# 3V8_Power_Regulator.net
KiCad netlist of a schematic drawn in Altium Designer
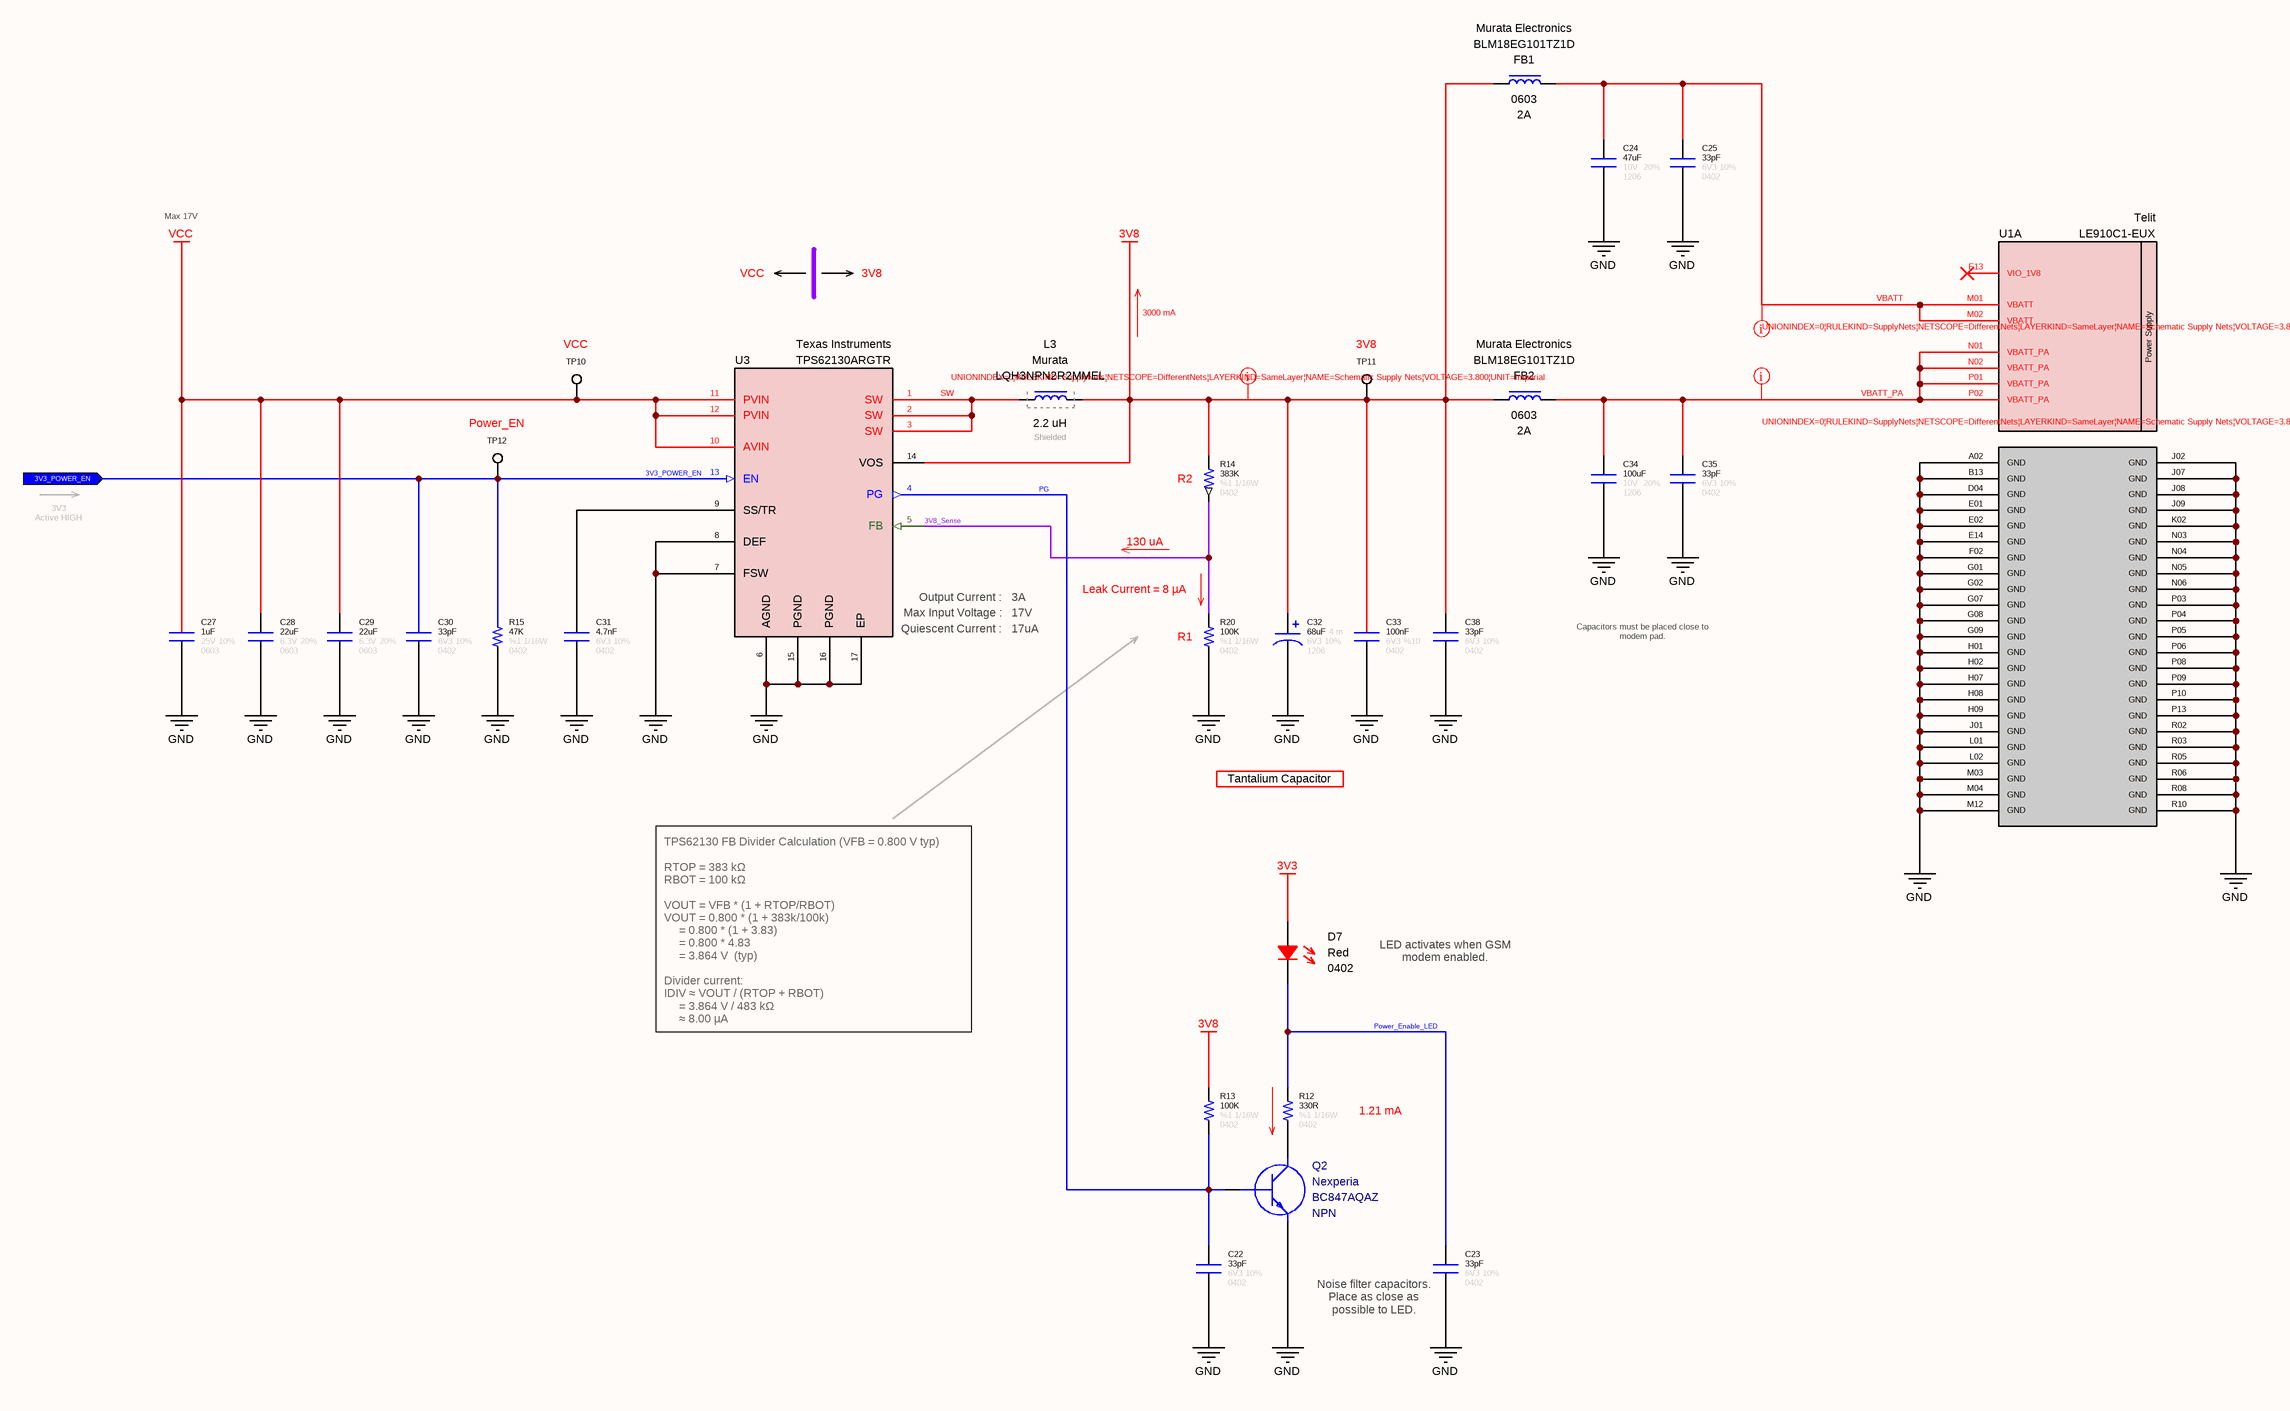
[diagram p0: 3V8_Power_Regulator.SchDoc]

(export (version "E")
  (design (tool "Eeschema 10.0.6"))
  (components
    (comp (ref "C22")
      (value "33pF")
      (footprint "CAPACITOR_0402")
      (description "Capacitor - 33pF [0402] (Ceramic)")
      (fields
        (field (name "MANUFACTURER PART NUMBER") "C0402C330J9RACAUTO")
        (field (name "TOLERANCE") "10%")
        (field (name "CASE") "0402")
        (field (name "VOLTAGE") "6V3")
      )
      (libsource (lib "P101DA_Library") (part "Capacitor - 33pF [0402-6V3]"))
    )
    (comp (ref "C23")
      (value "33pF")
      (footprint "CAPACITOR_0402")
      (description "Capacitor - 33pF [0402] (Ceramic)")
      (fields
        (field (name "MANUFACTURER PART NUMBER") "C0402C330J9RACAUTO")
        (field (name "TOLERANCE") "10%")
        (field (name "CASE") "0402")
        (field (name "VOLTAGE") "6V3")
      )
      (libsource (lib "P101DA_Library") (part "Capacitor - 33pF [0402-6V3]"))
    )
    (comp (ref "C24")
      (value "47uF")
      (footprint "CAPACITOR_1206")
      (description "Multilayer Ceramic Capacitors MLCC - SMD/SMT 47UF 10V 20% 1206")
      (fields
        (field (name "MANUFACTURER PART NUMBER") "C1206C476M8PAC")
        (field (name "TOLERANCE") "20%")
        (field (name "CASE") "1206")
        (field (name "VOLTAGE") "10V")
        (field (name "Comment") "Capacitor - 47uF [1206] (Ceramic)")
      )
      (libsource (lib "Akkoyun") (part "Capacitor - 47uF [1206-10V]"))
    )
    (comp (ref "C25")
      (value "33pF")
      (footprint "CAPACITOR_0402")
      (description "Capacitor - 33pF [0402] (Ceramic)")
      (fields
        (field (name "MANUFACTURER PART NUMBER") "C0402C330J9RACAUTO")
        (field (name "TOLERANCE") "10%")
        (field (name "CASE") "0402")
        (field (name "VOLTAGE") "6V3")
      )
      (libsource (lib "Akkoyun") (part "Capacitor - 33pF [0402-6V3]"))
    )
    (comp (ref "C27")
      (value "1uF")
      (footprint "CAPACITOR_0402")
      (description "Multilayer Ceramic Capacitors - SMD - 25V 1uF X7R 0603 10%")
      (fields
        (field (name "MANUFACTURER PART NUMBER") "GCJ188R71E105KA01D")
        (field (name "TOLERANCE") "10%")
        (field (name "CASE") "0603")
        (field (name "VOLTAGE") "25V")
        (field (name "Comment") "Capacitor - 1uF [0603] (Ceramic)")
      )
      (libsource (lib "Akkoyun") (part "Capacitor - 1uF [0603-25V]"))
    )
    (comp (ref "C28")
      (value "22uF")
      (footprint "CAPACITOR_0603")
      (description "Capacitor (MLCC) - 22uF / 6V3 / 0603")
      (fields
        (field (name "MANUFACTURER PART NUMBER") "GRM188R60J226MEA0D")
        (field (name "TOLERANCE") "20%")
        (field (name "CASE") "0603")
        (field (name "VOLTAGE") "6.3V")
        (field (name "Comment") "Capacitor - 22uF [0603] (MLCC)")
      )
      (libsource (lib "Akkoyun") (part "Capacitor - 22uF [0603-6V3]"))
    )
    (comp (ref "C29")
      (value "22uF")
      (footprint "CAPACITOR_0603")
      (description "Capacitor (MLCC) - 22uF / 6V3 / 0603")
      (fields
        (field (name "MANUFACTURER PART NUMBER") "GRM188R60J226MEA0D")
        (field (name "TOLERANCE") "20%")
        (field (name "CASE") "0603")
        (field (name "VOLTAGE") "6.3V")
        (field (name "Comment") "Capacitor - 22uF [0603] (MLCC)")
      )
      (libsource (lib "Akkoyun") (part "Capacitor - 22uF [0603-6V3]"))
    )
    (comp (ref "C30")
      (value "33pF")
      (footprint "CAPACITOR_0402")
      (description "Capacitor - 33pF [0402] (Ceramic)")
      (fields
        (field (name "MANUFACTURER PART NUMBER") "C0402C330J9RACAUTO")
        (field (name "TOLERANCE") "10%")
        (field (name "CASE") "0402")
        (field (name "VOLTAGE") "6V3")
      )
      (libsource (lib "Akkoyun") (part "Capacitor - 33pF [0402-6V3]"))
    )
    (comp (ref "C31")
      (value "4.7nF")
      (footprint "CAPACITOR_0402")
      (description "Capacitor (MLCC) - 4.7nF / 6V3 / 0402")
      (fields
        (field (name "MANUFACTURER PART NUMBER") "C0402C472K9RACTU")
        (field (name "TOLERANCE") "10%")
        (field (name "CASE") "0402")
        (field (name "VOLTAGE") "6V3")
        (field (name "Comment") "Capacitor - 4.7nF [0402] (MLCC)")
      )
      (libsource (lib "Akkoyun") (part "Capacitor - 4.7nF [0402-6V3]"))
    )
    (comp (ref "C32")
      (value "68uF")
      (footprint "CAPACITOR_1206 (Kemet)")
      (description "Capacitor (Tantalum) - 68uF / 6V3 / 1206")
      (fields
        (field (name "MANUFACTURER PART NUMBER") "T491A686K006AT")
        (field (name "ESR") "4 m")
        (field (name "TOLERANCE") "10%")
        (field (name "CASE") "1206")
        (field (name "VOLTAGE") "6V3")
        (field (name "Comment") "Capacitor - 68uF [1206] (Tantalum)")
      )
      (libsource (lib "Akkoyun") (part "Capacitor - 68uF [1206-6V3]"))
    )
    (comp (ref "C33")
      (value "100nF")
      (footprint "CAPACITOR_0402")
      (description "Capacitor - 100nF [0402-6V3] (Ceramic)")
      (fields
        (field (name "MANUFACTURER PART NUMBER") "04026D104KAT4A")
        (field (name "TOLERANCE") "%10")
        (field (name "VOLTAGE") "6V3")
        (field (name "CASE") "0402")
        (field (name "Comment") "Capacitor - 100nF [0402] (Ceramic)")
      )
      (libsource (lib "Akkoyun") (part "Capacitor - 100nF [0402-6V3]"))
    )
    (comp (ref "C34")
      (value "100uF")
      (footprint "CAPACITOR_1206")
      (description "Multilayer Ceramic Capacitors MLCC - SMD/SMT 100UF 10V 20% 1206")
      (fields
        (field (name "MANUFACTURER PART NUMBER") "GRM31CR61A107MEA8L")
        (field (name "TOLERANCE") "20%")
        (field (name "CASE") "1206")
        (field (name "VOLTAGE") "10V")
        (field (name "Comment") "Capacitor - 100uF [1206] (Ceramic)")
      )
      (libsource (lib "Akkoyun") (part "Capacitor - 100uF [1206-10V]"))
    )
    (comp (ref "C35")
      (value "33pF")
      (footprint "CAPACITOR_0402")
      (description "Capacitor - 33pF [0402] (Ceramic)")
      (fields
        (field (name "MANUFACTURER PART NUMBER") "C0402C330J9RACAUTO")
        (field (name "TOLERANCE") "10%")
        (field (name "CASE") "0402")
        (field (name "VOLTAGE") "6V3")
      )
      (libsource (lib "Akkoyun") (part "Capacitor - 33pF [0402-6V3]"))
    )
    (comp (ref "C38")
      (value "33pF")
      (footprint "CAPACITOR_0402")
      (description "Capacitor - 33pF [0402] (Ceramic)")
      (fields
        (field (name "MANUFACTURER PART NUMBER") "C0402C330J9RACAUTO")
        (field (name "TOLERANCE") "10%")
        (field (name "CASE") "0402")
        (field (name "VOLTAGE") "6V3")
      )
      (libsource (lib "Akkoyun") (part "Capacitor - 33pF [0402-6V3]"))
    )
    (comp (ref "D7")
      (value "SMD LED (Red)")
      (footprint "LED_0402")
      (description "Standard LEDs - SMD MINI-MOLD ULTRA COMPACT RED")
      (fields
        (field (name "MANUFACTURER PART NUMBER") "SML-P12VTT86R")
        (field (name "CASE") "0402")
        (field (name "COLOR") "Red")
      )
      (libsource (lib "P101DA_Library") (part "Diode - LED (0402-Red)"))
    )
    (comp (ref "FB1")
      (value "Ferrite Bead")
      (footprint "INDUCTOR_0603")
      (description "Ferrite Beads 0603 100ohms 2000mA Auto Infotainment")
      (fields
        (field (name "TOLERANCE") "25%")
        (field (name "MAXIMUM DC CURRENT") "2A")
        (field (name "CASE") "0603")
        (field (name "MANUFACTURER PART NUMBER") "BLM18EG101TZ1D")
        (field (name "MANUFACTURER NAME") "Murata Electronics")
      )
      (libsource (lib "Akkoyun") (part "Inductor - Ferrite Bead [SMD]"))
    )
    (comp (ref "FB2")
      (value "Ferrite Bead")
      (footprint "INDUCTOR_0603")
      (description "Ferrite Beads 0603 100ohms 2000mA Auto Infotainment")
      (fields
        (field (name "TOLERANCE") "25%")
        (field (name "MAXIMUM DC CURRENT") "2A")
        (field (name "CASE") "0603")
        (field (name "MANUFACTURER PART NUMBER") "BLM18EG101TZ1D")
        (field (name "MANUFACTURER NAME") "Murata Electronics")
      )
      (libsource (lib "Akkoyun") (part "Inductor - Ferrite Bead [SMD]"))
    )
    (comp (ref "L3")
      (value "2.2 uH")
      (footprint "LQH3NPN2R2MMEL")
      (description "1.52 A. Power Inductors - SMD 4.7 UH 20%")
      (fields
        (field (name "MANUFACTURER NAME") "Murata")
        (field (name "MANUFACTURER PART NUMBER") "LQH3NPN2R2MMEL")
        (field (name "PROTECTION") "Shielded")
        (field (name "Comment") "LQH3NPN2R2MMEL")
      )
      (libsource (lib "Akkoyun") (part "Inductor - LQH3NPN2R2MMEL"))
    )
    (comp (ref "Q2")
      (value "BC847AQAZ")
      (footprint "SOT1215")
      (description "Bipolar NPN Transistors")
      (fields
        (field (name "MANUFACTURER NAME") "Nexperia")
        (field (name "MANUFACTURER PART NUMBER") "BC847AQAZ")
        (field (name "POLARITY") "NPN")
      )
      (libsource (lib "P101DA_Library") (part "Transistor - BC847"))
    )
    (comp (ref "R12")
      (value "330R")
      (footprint "RESISTOR_0402")
      (description "Thick Film Resistors - SMD 1/16 W 330 Ohm 1%")
      (fields
        (field (name "MANUFACTURER PART NUMBER") "CRCW0402330RFKED")
        (field (name "CASE") "0402")
        (field (name "TOLERANCE") "%1")
        (field (name "POWER") "1/16W")
        (field (name "Comment") "330R - 0402 - %1 - 1/16W")
      )
      (libsource (lib "P101DA_Library") (part "Resistor - 330R [0402]"))
    )
    (comp (ref "R13")
      (value "100K")
      (footprint "RESISTOR_0402")
      (description "Thick Film Resistors - SMD 1/16 W 100 KOhm 1%")
      (fields
        (field (name "MANUFACTURER PART NUMBER") "CRCW0402100KFKED")
        (field (name "TOLERANCE") "%1")
        (field (name "CASE") "0402")
        (field (name "POWER") "1/16W")
        (field (name "Comment") "100K - 0402 - %1 - 1/16W")
      )
      (libsource (lib "Akkoyun") (part "Resistor - 100K [0402]"))
    )
    (comp (ref "R14")
      (value "383K")
      (footprint "RESISTOR_0402")
      (description "Thick Film Resistors - SMD 1/16 W 383 KOhm 1%")
      (fields
        (field (name "MANUFACTURER PART NUMBER") "CRCW0402383KFKED")
        (field (name "TOLERANCE") "%1")
        (field (name "CASE") "0402")
        (field (name "POWER") "1/16W")
        (field (name "Comment") "383K - 0402 - %1 - 1/16W")
      )
      (libsource (lib "Akkoyun") (part "Resistor - 383K [0402]"))
    )
    (comp (ref "R15")
      (value "47K")
      (footprint "RESISTOR_0402")
      (description "Thick Film Resistors - SMD 1/16 W 47 KOhm 1%")
      (fields
        (field (name "MANUFACTURER PART NUMBER") "CRCW040247K0FKED")
        (field (name "TOLERANCE") "%1")
        (field (name "CASE") "0402")
        (field (name "POWER") "1/16W")
        (field (name "Comment") "47K - 0402 - %1 - 1/16W")
      )
      (libsource (lib "Akkoyun") (part "Resistor - 47K [0402]"))
    )
    (comp (ref "R20")
      (value "100K")
      (footprint "RESISTOR_0402")
      (description "Thick Film Resistors - SMD 1/16 W 100 KOhm 1%")
      (fields
        (field (name "MANUFACTURER PART NUMBER") "CRCW0402100KFKED")
        (field (name "TOLERANCE") "%1")
        (field (name "CASE") "0402")
        (field (name "POWER") "1/16W")
        (field (name "Comment") "100K - 0402 - %1 - 1/16W")
      )
      (libsource (lib "Akkoyun") (part "Resistor - 100K [0402]"))
    )
    (comp (ref "TP10")
      (value "VCC")
      (footprint "TP")
      (description "Test Point")
      (libsource (lib "Akkoyun") (part "PCB - Test Point"))
    )
    (comp (ref "TP11")
      (value "3V8")
      (footprint "TP")
      (description "Test Point")
      (libsource (lib "Akkoyun") (part "PCB - Test Point"))
    )
    (comp (ref "TP12")
      (value "Power_EN")
      (footprint "TP")
      (description "Test Point")
      (libsource (lib "Akkoyun") (part "PCB - Test Point"))
    )
    (comp (ref "U1")
      (value "LE910C1-EUX LTE GSM Module")
      (footprint "LE910 GSM Modem")
      (description "Telit LE910C1-EUX LTE/2G GSM Module")
      (fields
        (field (name "MANUFACTURER PART NUMBER") "LE910C1-EUX")
        (field (name "MANUFACTURER NAME") "Telit")
      )
      (libsource (lib "Akkoyun") (part "IC - LE910C1-EUX"))
    )
    (comp (ref "U3")
      (value "TPS62130ARGTR")
      (footprint "VQFN-EP-16")
      (description "Switching Voltage Regulators 3-17V 3A Step Down Converter.")
      (fields
        (field (name "MANUFACTURER PART NUMBER") "TPS62130ARGTR")
        (field (name "MANUFACTURER NAME") "Texas Instruments")
        (field (name "OUTPUT CURRENT") "3A")
        (field (name "INPUT VOLTAGE - MAX") "17V")
        (field (name "QUIESCENT CURRENT") "17uA")
      )
      (libsource (lib "Akkoyun") (part "IC - TPS62130"))
    )
  )
  (nets
    (net (code "1") (name "/3V3_POWER_EN") (class "Default")
      (node (ref "C30") (pin "2") (pinfunction "2_2") (pintype "passive"))
      (node (ref "R15") (pin "2") (pinfunction "2_2") (pintype "passive"))
      (node (ref "TP12") (pin "1") (pinfunction "1_1") (pintype "passive"))
      (node (ref "U3") (pin "13") (pinfunction "EN_13") (pintype "input"))
    )
    (net (code "2") (name "/3V8_Sense") (class "Default")
      (node (ref "R14") (pin "1") (pinfunction "1_1") (pintype "output"))
      (node (ref "R20") (pin "2") (pinfunction "2_2") (pintype "passive"))
      (node (ref "U3") (pin "5") (pinfunction "FB_5") (pintype "input"))
    )
    (net (code "3") (name "/PG") (class "Default")
      (node (ref "C22") (pin "2") (pinfunction "2_2") (pintype "passive"))
      (node (ref "Q2") (pin "1") (pinfunction "B_1") (pintype "passive"))
      (node (ref "R13") (pin "1") (pinfunction "1_1") (pintype "passive"))
      (node (ref "U3") (pin "4") (pinfunction "PG_4") (pintype "output"))
    )
    (net (code "4") (name "/Power_Enable_LED") (class "Default")
      (node (ref "C23") (pin "2") (pinfunction "2_2") (pintype "passive"))
      (node (ref "D7") (pin "1") (pinfunction "1_1") (pintype "passive"))
      (node (ref "R12") (pin "2") (pinfunction "2_2") (pintype "passive"))
    )
    (net (code "5") (name "/SW") (class "Default")
      (node (ref "L3") (pin "1") (pinfunction "1_1") (pintype "passive"))
      (node (ref "U3") (pin "1") (pinfunction "SW_1") (pintype "power_in"))
      (node (ref "U3") (pin "2") (pinfunction "SW_2") (pintype "power_in"))
      (node (ref "U3") (pin "3") (pinfunction "SW_3") (pintype "power_in"))
    )
    (net (code "6") (name "/VBATT") (class "Default")
      (node (ref "C24") (pin "2") (pinfunction "2_2") (pintype "passive"))
      (node (ref "C25") (pin "2") (pinfunction "2_2") (pintype "passive"))
      (node (ref "FB1") (pin "2") (pinfunction "2_2") (pintype "passive"))
      (node (ref "U1") (pin "M01") (pinfunction "VBATT_M01") (pintype "power_in"))
      (node (ref "U1") (pin "M02") (pinfunction "VBATT_M02") (pintype "power_in"))
    )
    (net (code "7") (name "/VBATT_PA") (class "Default")
      (node (ref "C34") (pin "2") (pinfunction "2_2") (pintype "passive"))
      (node (ref "C35") (pin "2") (pinfunction "2_2") (pintype "passive"))
      (node (ref "FB2") (pin "2") (pinfunction "2_2") (pintype "passive"))
      (node (ref "U1") (pin "N01") (pinfunction "VBATT_PA_N01") (pintype "power_in"))
      (node (ref "U1") (pin "N02") (pinfunction "VBATT_PA_N02") (pintype "power_in"))
      (node (ref "U1") (pin "P01") (pinfunction "VBATT_PA_P01") (pintype "power_in"))
      (node (ref "U1") (pin "P02") (pinfunction "VBATT_PA_P02") (pintype "power_in"))
    )
    (net (code "8") (name "3V3") (class "Default")
      (node (ref "D7") (pin "2") (pinfunction "2_2") (pintype "passive"))
    )
    (net (code "9") (name "3V8") (class "Default")
      (node (ref "C32") (pin "1") (pinfunction "1_1") (pintype "passive"))
      (node (ref "C33") (pin "2") (pinfunction "2_2") (pintype "passive"))
      (node (ref "C38") (pin "2") (pinfunction "2_2") (pintype "passive"))
      (node (ref "FB1") (pin "1") (pinfunction "1_1") (pintype "passive"))
      (node (ref "FB2") (pin "1") (pinfunction "1_1") (pintype "passive"))
      (node (ref "L3") (pin "2") (pinfunction "2_2") (pintype "passive"))
      (node (ref "R13") (pin "2") (pinfunction "2_2") (pintype "passive"))
      (node (ref "R14") (pin "2") (pinfunction "2_2") (pintype "passive"))
      (node (ref "TP11") (pin "1") (pinfunction "1_1") (pintype "passive"))
      (node (ref "U3") (pin "14") (pinfunction "VOS_14") (pintype "passive"))
    )
    (net (code "10") (name "GND") (class "Default")
      (node (ref "C22") (pin "1") (pinfunction "1_1") (pintype "passive"))
      (node (ref "C23") (pin "1") (pinfunction "1_1") (pintype "passive"))
      (node (ref "C24") (pin "1") (pinfunction "1_1") (pintype "passive"))
      (node (ref "C25") (pin "1") (pinfunction "1_1") (pintype "passive"))
      (node (ref "C27") (pin "1") (pinfunction "1_1") (pintype "passive"))
      (node (ref "C28") (pin "1") (pinfunction "1_1") (pintype "passive"))
      (node (ref "C29") (pin "1") (pinfunction "1_1") (pintype "passive"))
      (node (ref "C30") (pin "1") (pinfunction "1_1") (pintype "passive"))
      (node (ref "C31") (pin "1") (pinfunction "1_1") (pintype "passive"))
      (node (ref "C32") (pin "2") (pinfunction "2_2") (pintype "passive"))
      (node (ref "C33") (pin "1") (pinfunction "1_1") (pintype "passive"))
      (node (ref "C34") (pin "1") (pinfunction "1_1") (pintype "passive"))
      (node (ref "C35") (pin "1") (pinfunction "1_1") (pintype "passive"))
      (node (ref "C38") (pin "1") (pinfunction "1_1") (pintype "passive"))
      (node (ref "Q2") (pin "2") (pinfunction "E_2") (pintype "passive"))
      (node (ref "R15") (pin "1") (pinfunction "1_1") (pintype "passive"))
      (node (ref "R20") (pin "1") (pinfunction "1_1") (pintype "passive"))
      (node (ref "U1") (pin "A02") (pinfunction "GND_A02") (pintype "power_in"))
      (node (ref "U1") (pin "B13") (pinfunction "GND_B13") (pintype "power_in"))
      (node (ref "U1") (pin "D04") (pinfunction "GND_D04") (pintype "power_in"))
      (node (ref "U1") (pin "E01") (pinfunction "GND_E01") (pintype "power_in"))
      (node (ref "U1") (pin "E02") (pinfunction "GND_E02") (pintype "power_in"))
      (node (ref "U1") (pin "E14") (pinfunction "GND_E14") (pintype "power_in"))
      (node (ref "U1") (pin "F02") (pinfunction "GND_F02") (pintype "power_in"))
      (node (ref "U1") (pin "G01") (pinfunction "GND_G01") (pintype "power_in"))
      (node (ref "U1") (pin "G02") (pinfunction "GND_G02") (pintype "power_in"))
      (node (ref "U1") (pin "G07") (pinfunction "GND_G07") (pintype "power_in"))
      (node (ref "U1") (pin "G08") (pinfunction "GND_G08") (pintype "power_in"))
      (node (ref "U1") (pin "G09") (pinfunction "GND_G09") (pintype "power_in"))
      (node (ref "U1") (pin "H01") (pinfunction "GND_H01") (pintype "power_in"))
      (node (ref "U1") (pin "H02") (pinfunction "GND_H02") (pintype "power_in"))
      (node (ref "U1") (pin "H07") (pinfunction "GND_H07") (pintype "power_in"))
      (node (ref "U1") (pin "H08") (pinfunction "GND_H08") (pintype "power_in"))
      (node (ref "U1") (pin "H09") (pinfunction "GND_H09") (pintype "power_in"))
      (node (ref "U1") (pin "J01") (pinfunction "GND_J01") (pintype "power_in"))
      (node (ref "U1") (pin "J02") (pinfunction "GND_J02") (pintype "power_in"))
      (node (ref "U1") (pin "J07") (pinfunction "GND_J07") (pintype "power_in"))
      (node (ref "U1") (pin "J08") (pinfunction "GND_J08") (pintype "power_in"))
      (node (ref "U1") (pin "J09") (pinfunction "GND_J09") (pintype "power_in"))
      (node (ref "U1") (pin "K02") (pinfunction "GND_K02") (pintype "power_in"))
      (node (ref "U1") (pin "L01") (pinfunction "GND_L01") (pintype "power_in"))
      (node (ref "U1") (pin "L02") (pinfunction "GND_L02") (pintype "power_in"))
      (node (ref "U1") (pin "M03") (pinfunction "GND_M03") (pintype "power_in"))
      (node (ref "U1") (pin "M04") (pinfunction "GND_M04") (pintype "power_in"))
      (node (ref "U1") (pin "M12") (pinfunction "GND_M12") (pintype "power_in"))
      (node (ref "U1") (pin "N03") (pinfunction "GND_N03") (pintype "power_in"))
      (node (ref "U1") (pin "N04") (pinfunction "GND_N04") (pintype "power_in"))
      (node (ref "U1") (pin "N05") (pinfunction "GND_N05") (pintype "power_in"))
      (node (ref "U1") (pin "N06") (pinfunction "GND_N06") (pintype "power_in"))
      (node (ref "U1") (pin "P03") (pinfunction "GND_P03") (pintype "power_in"))
      (node (ref "U1") (pin "P04") (pinfunction "GND_P04") (pintype "power_in"))
      (node (ref "U1") (pin "P05") (pinfunction "GND_P05") (pintype "power_in"))
      (node (ref "U1") (pin "P06") (pinfunction "GND_P06") (pintype "power_in"))
      (node (ref "U1") (pin "P08") (pinfunction "GND_P08") (pintype "power_in"))
      (node (ref "U1") (pin "P09") (pinfunction "GND_P09") (pintype "power_in"))
      (node (ref "U1") (pin "P10") (pinfunction "GND_P10") (pintype "power_in"))
      (node (ref "U1") (pin "P13") (pinfunction "GND_P13") (pintype "power_in"))
      (node (ref "U1") (pin "R02") (pinfunction "GND_R02") (pintype "power_in"))
      (node (ref "U1") (pin "R03") (pinfunction "GND_R03") (pintype "power_in"))
      (node (ref "U1") (pin "R05") (pinfunction "GND_R05") (pintype "power_in"))
      (node (ref "U1") (pin "R06") (pinfunction "GND_R06") (pintype "power_in"))
      (node (ref "U1") (pin "R08") (pinfunction "GND_R08") (pintype "power_in"))
      (node (ref "U1") (pin "R10") (pinfunction "GND_R10") (pintype "power_in"))
      (node (ref "U3") (pin "15") (pinfunction "PGND_15") (pintype "power_in"))
      (node (ref "U3") (pin "16") (pinfunction "PGND_16") (pintype "power_in"))
      (node (ref "U3") (pin "17") (pinfunction "EP_17") (pintype "power_in"))
      (node (ref "U3") (pin "6") (pinfunction "AGND_6") (pintype "power_in"))
      (node (ref "U3") (pin "7") (pinfunction "FSW_7") (pintype "passive"))
      (node (ref "U3") (pin "8") (pinfunction "DEF_8") (pintype "passive"))
    )
    (net (code "11") (name "Net-(Q2-C)") (class "Default")
      (node (ref "Q2") (pin "3") (pinfunction "C_3") (pintype "passive"))
      (node (ref "R12") (pin "1") (pinfunction "1_1") (pintype "passive"))
    )
    (net (code "12") (name "Net-(U3-SS{slash}TR)") (class "Default")
      (node (ref "C31") (pin "2") (pinfunction "2_2") (pintype "passive"))
      (node (ref "U3") (pin "9") (pinfunction "SS/TR_9") (pintype "passive"))
    )
    (net (code "13") (name "VCC") (class "Default")
      (node (ref "C27") (pin "2") (pinfunction "2_2") (pintype "passive"))
      (node (ref "C28") (pin "2") (pinfunction "2_2") (pintype "passive"))
      (node (ref "C29") (pin "2") (pinfunction "2_2") (pintype "passive"))
      (node (ref "TP10") (pin "1") (pinfunction "1_1") (pintype "passive"))
      (node (ref "U3") (pin "10") (pinfunction "AVIN_10") (pintype "power_in"))
      (node (ref "U3") (pin "11") (pinfunction "PVIN_11") (pintype "power_in"))
      (node (ref "U3") (pin "12") (pinfunction "PVIN_12") (pintype "power_in"))
    )
    (net (code "14") (name "unconnected-(U1A-VIO_1V8-PadE13)") (class "Default")
      (node (ref "U1") (pin "E13") (pinfunction "VIO_1V8_E13") (pintype "power_in+no_connect"))
    )
  )
)
